# 3DBoard.net
KiCad netlist of a schematic drawn in EAGLE
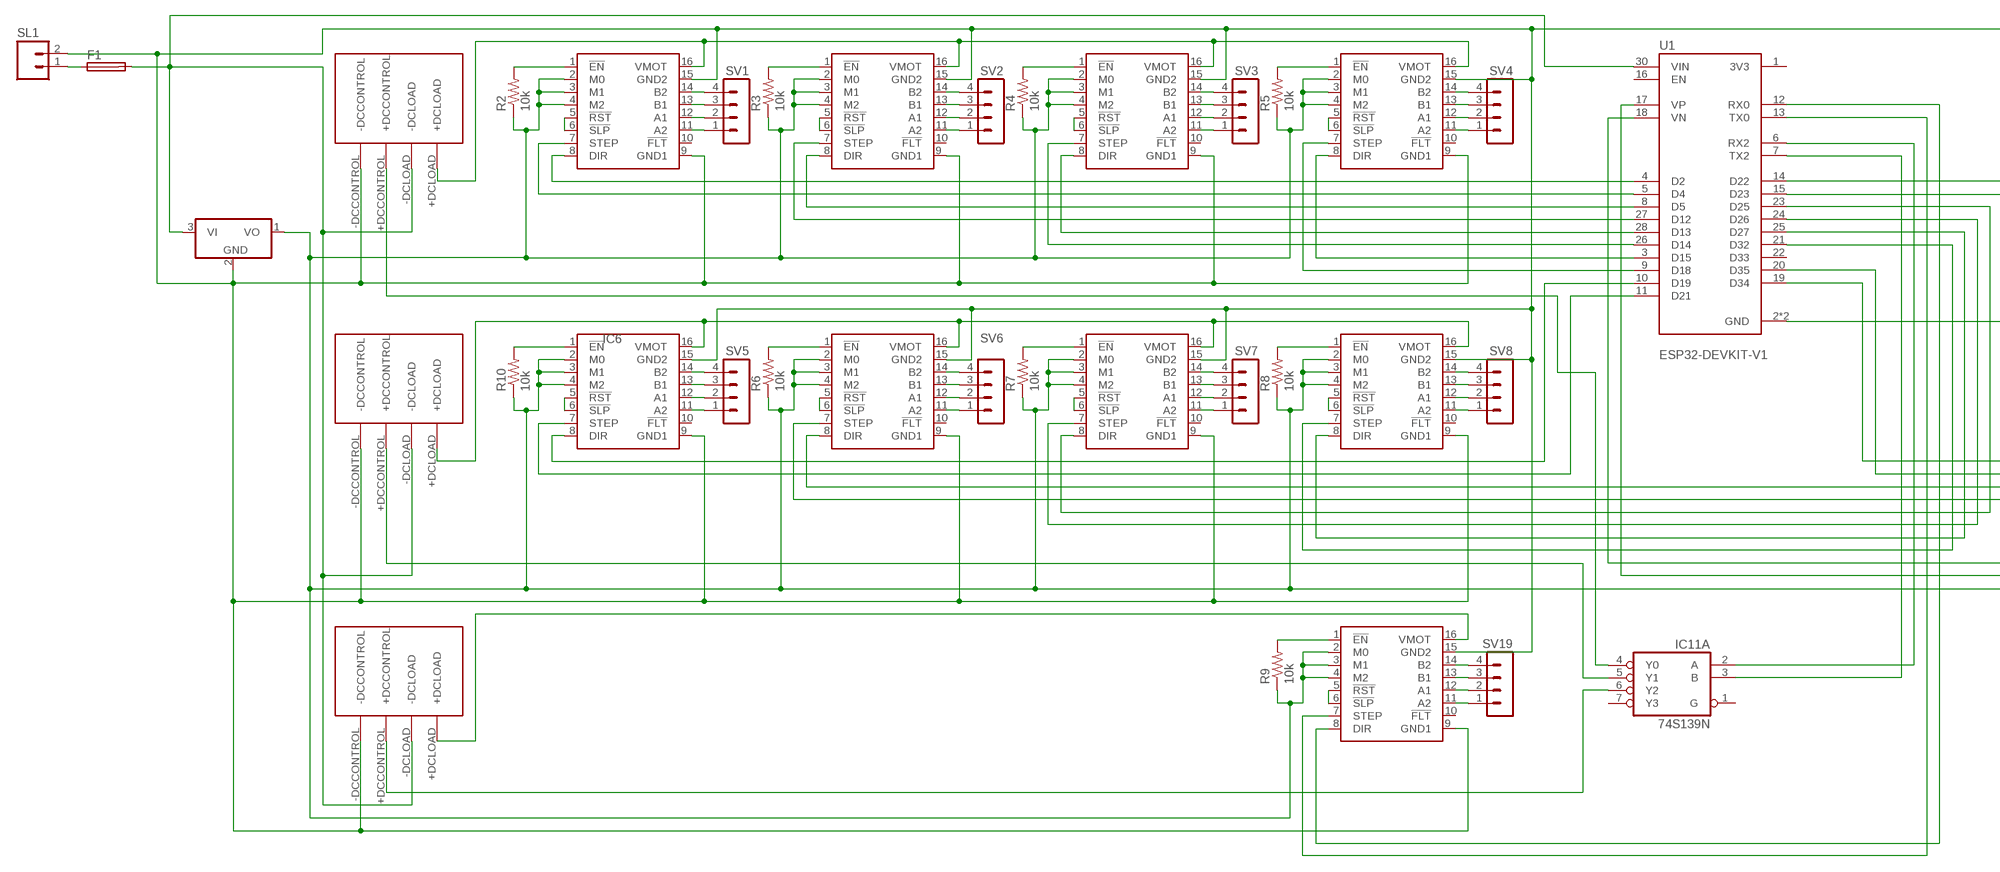
[diagram p0: schematic, sheet 1, part 1 of 2]
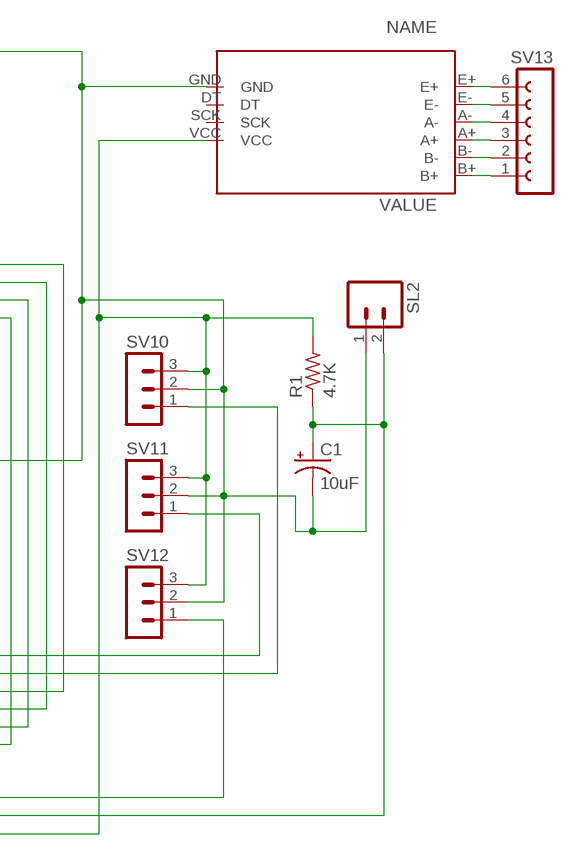
[diagram p1: schematic, sheet 1, part 2 of 2]

(export (version "E")
  (design (tool "Eeschema 10.0.6"))
  (components
    (comp (ref "C1")
      (value "10uF")
      (footprint "eagle-import:B45181B")
      (libsource (lib "eagle-import") (part "CPOL-USB45181B"))
    )
    (comp (ref "F1")
      (value "GSH15")
      (footprint "eagle-import:GSH15")
      (fields (field (name "MPN") "64900001039"))
      (libsource (lib "eagle-import") (part "GSH15"))
    )
    (comp (ref "IC1")
      (value "78L05Z")
      (footprint "eagle-import:TO92")
      (libsource (lib "eagle-import") (part "78ZL05"))
    )
    (comp (ref "IC2")
      (value "2987-DRV8825")
      (footprint "eagle-import:DRV8825")
      (libsource (lib "eagle-import") (part "2987-DRV8825"))
    )
    (comp (ref "IC3")
      (value "2987-DRV8825")
      (footprint "eagle-import:DRV8825")
      (libsource (lib "eagle-import") (part "2987-DRV8825"))
    )
    (comp (ref "IC4")
      (value "2987-DRV8825")
      (footprint "eagle-import:DRV8825")
      (libsource (lib "eagle-import") (part "2987-DRV8825"))
    )
    (comp (ref "IC5")
      (value "2987-DRV8825")
      (footprint "eagle-import:DRV8825")
      (libsource (lib "eagle-import") (part "2987-DRV8825"))
    )
    (comp (ref "IC6")
      (value "2987-DRV8825")
      (footprint "eagle-import:DRV8825")
      (libsource (lib "eagle-import") (part "2987-DRV8825"))
    )
    (comp (ref "IC7")
      (value "2987-DRV8825")
      (footprint "eagle-import:DRV8825")
      (libsource (lib "eagle-import") (part "2987-DRV8825"))
    )
    (comp (ref "IC8")
      (value "2987-DRV8825")
      (footprint "eagle-import:DRV8825")
      (libsource (lib "eagle-import") (part "2987-DRV8825"))
    )
    (comp (ref "IC9")
      (value "2987-DRV8825")
      (footprint "eagle-import:DRV8825")
      (libsource (lib "eagle-import") (part "2987-DRV8825"))
    )
    (comp (ref "IC10")
      (value "2987-DRV8825")
      (footprint "eagle-import:DRV8825")
      (libsource (lib "eagle-import") (part "2987-DRV8825"))
    )
    (comp (ref "IC11")
      (value "74S139N")
      (footprint "eagle-import:DIL16")
      (libsource (lib "eagle-import") (part "74139NS"))
    )
    (comp (ref "R1")
      (value "4.7K")
      (footprint "eagle-import:0204_7")
      (libsource (lib "eagle-import") (part "R-US_0204/7"))
    )
    (comp (ref "R2")
      (value "10k")
      (footprint "eagle-import:0204_7")
      (libsource (lib "eagle-import") (part "R-US_0204/7"))
    )
    (comp (ref "R3")
      (value "10k")
      (footprint "eagle-import:0204_7")
      (libsource (lib "eagle-import") (part "R-US_0204/7"))
    )
    (comp (ref "R4")
      (value "10k")
      (footprint "eagle-import:0204_7")
      (libsource (lib "eagle-import") (part "R-US_0204/7"))
    )
    (comp (ref "R5")
      (value "10k")
      (footprint "eagle-import:0204_7")
      (libsource (lib "eagle-import") (part "R-US_0204/7"))
    )
    (comp (ref "R6")
      (value "10k")
      (footprint "eagle-import:0204_7")
      (libsource (lib "eagle-import") (part "R-US_0204/7"))
    )
    (comp (ref "R7")
      (value "10k")
      (footprint "eagle-import:0204_7")
      (libsource (lib "eagle-import") (part "R-US_0204/7"))
    )
    (comp (ref "R8")
      (value "10k")
      (footprint "eagle-import:0204_7")
      (libsource (lib "eagle-import") (part "R-US_0204/7"))
    )
    (comp (ref "R9")
      (value "10k")
      (footprint "eagle-import:0204_7")
      (libsource (lib "eagle-import") (part "R-US_0204/7"))
    )
    (comp (ref "R10")
      (value "10k")
      (footprint "eagle-import:0204_7")
      (libsource (lib "eagle-import") (part "R-US_0204/7"))
    )
    (comp (ref "SL1")
      (value "M02")
      (footprint "eagle-import:02P")
      (libsource (lib "eagle-import") (part "M02"))
    )
    (comp (ref "SL2")
      (value "M02")
      (footprint "eagle-import:02P")
      (libsource (lib "eagle-import") (part "M02"))
    )
    (comp (ref "SV1")
      (value "MA04-1")
      (footprint "eagle-import:MA04-1")
      (libsource (lib "eagle-import") (part "MA04-1"))
    )
    (comp (ref "SV2")
      (value "MA04-1")
      (footprint "eagle-import:MA04-1")
      (libsource (lib "eagle-import") (part "MA04-1"))
    )
    (comp (ref "SV3")
      (value "MA04-1")
      (footprint "eagle-import:MA04-1")
      (libsource (lib "eagle-import") (part "MA04-1"))
    )
    (comp (ref "SV4")
      (value "MA04-1")
      (footprint "eagle-import:MA04-1")
      (libsource (lib "eagle-import") (part "MA04-1"))
    )
    (comp (ref "SV5")
      (value "MA04-1")
      (footprint "eagle-import:MA04-1")
      (libsource (lib "eagle-import") (part "MA04-1"))
    )
    (comp (ref "SV6")
      (value "MA04-1")
      (footprint "eagle-import:MA04-1")
      (libsource (lib "eagle-import") (part "MA04-1"))
    )
    (comp (ref "SV7")
      (value "MA04-1")
      (footprint "eagle-import:MA04-1")
      (libsource (lib "eagle-import") (part "MA04-1"))
    )
    (comp (ref "SV8")
      (value "MA04-1")
      (footprint "eagle-import:MA04-1")
      (libsource (lib "eagle-import") (part "MA04-1"))
    )
    (comp (ref "SV10")
      (value "MA03-1")
      (footprint "eagle-import:MA03-1")
      (libsource (lib "eagle-import") (part "MA03-1"))
    )
    (comp (ref "SV11")
      (value "MA03-1")
      (footprint "eagle-import:MA03-1")
      (libsource (lib "eagle-import") (part "MA03-1"))
    )
    (comp (ref "SV12")
      (value "MA03-1")
      (footprint "eagle-import:MA03-1")
      (libsource (lib "eagle-import") (part "MA03-1"))
    )
    (comp (ref "SV13")
      (value "FE06-1")
      (footprint "eagle-import:FE06")
      (libsource (lib "eagle-import") (part "FE06-1"))
    )
    (comp (ref "SV19")
      (value "MA04-1")
      (footprint "eagle-import:MA04-1")
      (libsource (lib "eagle-import") (part "MA04-1"))
    )
    (comp (ref "U$2")
      (value "HX711A")
      (footprint "eagle-import:HX711")
      (libsource (lib "eagle-import") (part "HX711A"))
    )
    (comp (ref "U$3")
      (value "CMX60D10")
      (footprint "eagle-import:SIP-4")
      (fields (field (name "MF") "Sensata-Crydom"))
      (libsource (lib "eagle-import") (part "CMX60D10"))
    )
    (comp (ref "U$4")
      (value "CMX60D10")
      (footprint "eagle-import:SIP-4")
      (fields (field (name "MF") "Sensata-Crydom"))
      (libsource (lib "eagle-import") (part "CMX60D10"))
    )
    (comp (ref "U$5")
      (value "CMX60D10")
      (footprint "eagle-import:SIP-4")
      (fields (field (name "MF") "Sensata-Crydom"))
      (libsource (lib "eagle-import") (part "CMX60D10"))
    )
    (comp (ref "U1")
      (value "ESP32-DEVKIT-V1")
      (footprint "eagle-import:MODULE_ESP32_DEVKIT_V1")
      (fields (field (name "MF") "Do it"))
      (libsource (lib "eagle-import") (part "ESP32-DEVKIT-V1"))
    )
  )
  (nets
    (net (code "1") (name "Net-(F1-Pad1)") (class "Default")
      (node (ref "F1") (pin "1") (pinfunction "1_1") (pintype "passive"))
      (node (ref "SL1") (pin "1") (pinfunction "1_1") (pintype "passive"))
    )
    (net (code "2") (name "Net-(IC1-GND)") (class "Default")
      (node (ref "C1") (pin "-") (pinfunction "-_-") (pintype "passive"))
      (node (ref "IC1") (pin "2") (pinfunction "GND_2") (pintype "passive"))
      (node (ref "IC10") (pin "15") (pinfunction "GND2_15") (pintype "power_in"))
      (node (ref "IC10") (pin "9") (pinfunction "GND1_9") (pintype "power_in"))
      (node (ref "IC2") (pin "15") (pinfunction "GND2_15") (pintype "power_in"))
      (node (ref "IC2") (pin "9") (pinfunction "GND1_9") (pintype "power_in"))
      (node (ref "IC3") (pin "15") (pinfunction "GND2_15") (pintype "power_in"))
      (node (ref "IC3") (pin "9") (pinfunction "GND1_9") (pintype "power_in"))
      (node (ref "IC4") (pin "15") (pinfunction "GND2_15") (pintype "power_in"))
      (node (ref "IC4") (pin "9") (pinfunction "GND1_9") (pintype "power_in"))
      (node (ref "IC5") (pin "15") (pinfunction "GND2_15") (pintype "power_in"))
      (node (ref "IC5") (pin "9") (pinfunction "GND1_9") (pintype "power_in"))
      (node (ref "IC6") (pin "15") (pinfunction "GND2_15") (pintype "power_in"))
      (node (ref "IC6") (pin "9") (pinfunction "GND1_9") (pintype "power_in"))
      (node (ref "IC7") (pin "15") (pinfunction "GND2_15") (pintype "power_in"))
      (node (ref "IC7") (pin "9") (pinfunction "GND1_9") (pintype "power_in"))
      (node (ref "IC8") (pin "15") (pinfunction "GND2_15") (pintype "power_in"))
      (node (ref "IC8") (pin "9") (pinfunction "GND1_9") (pintype "power_in"))
      (node (ref "IC9") (pin "15") (pinfunction "GND2_15") (pintype "power_in"))
      (node (ref "IC9") (pin "9") (pinfunction "GND1_9") (pintype "power_in"))
      (node (ref "SL1") (pin "2") (pinfunction "2_2") (pintype "passive"))
      (node (ref "SL2") (pin "1") (pinfunction "1_1") (pintype "passive"))
      (node (ref "SV10") (pin "2") (pinfunction "2_2") (pintype "passive"))
      (node (ref "SV11") (pin "2") (pinfunction "2_2") (pintype "passive"))
      (node (ref "SV12") (pin "2") (pinfunction "2_2") (pintype "passive"))
      (node (ref "U$2") (pin "GND") (pinfunction "GND_GND") (pintype "bidirectional"))
      (node (ref "U$3") (pin "-DCCONTROL") (pinfunction "-DCCONTROL_-DCCONTROL") (pintype "bidirectional"))
      (node (ref "U$4") (pin "-DCCONTROL") (pinfunction "-DCCONTROL_-DCCONTROL") (pintype "bidirectional"))
      (node (ref "U$5") (pin "-DCCONTROL") (pinfunction "-DCCONTROL_-DCCONTROL") (pintype "bidirectional"))
      (node (ref "U1") (pin "2") (pinfunction "GND_2") (pintype "power_in"))
      (node (ref "U1") (pin "29") (pinfunction "GND_29") (pintype "power_in"))
    )
    (net (code "3") (name "Net-(IC1-VI)") (class "Default")
      (node (ref "F1") (pin "2") (pinfunction "2_2") (pintype "passive"))
      (node (ref "IC1") (pin "3") (pinfunction "VI_3") (pintype "input"))
      (node (ref "U$3") (pin "-DCLOAD") (pinfunction "-DCLOAD_-DCLOAD") (pintype "bidirectional"))
      (node (ref "U$4") (pin "-DCLOAD") (pinfunction "-DCLOAD_-DCLOAD") (pintype "bidirectional"))
      (node (ref "U$5") (pin "-DCLOAD") (pinfunction "-DCLOAD_-DCLOAD") (pintype "bidirectional"))
      (node (ref "U1") (pin "30") (pinfunction "VIN_30") (pintype "input"))
    )
    (net (code "4") (name "Net-(IC1-VO)") (class "Default")
      (node (ref "IC1") (pin "1") (pinfunction "VO_1") (pintype "passive"))
      (node (ref "IC10") (pin "2") (pinfunction "M0_2") (pintype "passive"))
      (node (ref "IC10") (pin "3") (pinfunction "M1_3") (pintype "passive"))
      (node (ref "IC10") (pin "4") (pinfunction "M2_4") (pintype "passive"))
      (node (ref "IC2") (pin "2") (pinfunction "M0_2") (pintype "passive"))
      (node (ref "IC2") (pin "3") (pinfunction "M1_3") (pintype "passive"))
      (node (ref "IC2") (pin "4") (pinfunction "M2_4") (pintype "passive"))
      (node (ref "IC3") (pin "2") (pinfunction "M0_2") (pintype "passive"))
      (node (ref "IC3") (pin "3") (pinfunction "M1_3") (pintype "passive"))
      (node (ref "IC3") (pin "4") (pinfunction "M2_4") (pintype "passive"))
      (node (ref "IC4") (pin "2") (pinfunction "M0_2") (pintype "passive"))
      (node (ref "IC4") (pin "3") (pinfunction "M1_3") (pintype "passive"))
      (node (ref "IC4") (pin "4") (pinfunction "M2_4") (pintype "passive"))
      (node (ref "IC5") (pin "2") (pinfunction "M0_2") (pintype "passive"))
      (node (ref "IC5") (pin "3") (pinfunction "M1_3") (pintype "passive"))
      (node (ref "IC5") (pin "4") (pinfunction "M2_4") (pintype "passive"))
      (node (ref "IC6") (pin "2") (pinfunction "M0_2") (pintype "passive"))
      (node (ref "IC6") (pin "3") (pinfunction "M1_3") (pintype "passive"))
      (node (ref "IC6") (pin "4") (pinfunction "M2_4") (pintype "passive"))
      (node (ref "IC7") (pin "2") (pinfunction "M0_2") (pintype "passive"))
      (node (ref "IC7") (pin "3") (pinfunction "M1_3") (pintype "passive"))
      (node (ref "IC7") (pin "4") (pinfunction "M2_4") (pintype "passive"))
      (node (ref "IC8") (pin "2") (pinfunction "M0_2") (pintype "passive"))
      (node (ref "IC8") (pin "3") (pinfunction "M1_3") (pintype "passive"))
      (node (ref "IC8") (pin "4") (pinfunction "M2_4") (pintype "passive"))
      (node (ref "IC9") (pin "2") (pinfunction "M0_2") (pintype "passive"))
      (node (ref "IC9") (pin "3") (pinfunction "M1_3") (pintype "passive"))
      (node (ref "IC9") (pin "4") (pinfunction "M2_4") (pintype "passive"))
      (node (ref "R1") (pin "2") (pinfunction "2_2") (pintype "passive"))
      (node (ref "R10") (pin "1") (pinfunction "1_1") (pintype "passive"))
      (node (ref "R2") (pin "1") (pinfunction "1_1") (pintype "passive"))
      (node (ref "R3") (pin "1") (pinfunction "1_1") (pintype "passive"))
      (node (ref "R4") (pin "1") (pinfunction "1_1") (pintype "passive"))
      (node (ref "R5") (pin "1") (pinfunction "1_1") (pintype "passive"))
      (node (ref "R6") (pin "1") (pinfunction "1_1") (pintype "passive"))
      (node (ref "R7") (pin "1") (pinfunction "1_1") (pintype "passive"))
      (node (ref "R8") (pin "1") (pinfunction "1_1") (pintype "passive"))
      (node (ref "R9") (pin "1") (pinfunction "1_1") (pintype "passive"))
      (node (ref "SV10") (pin "3") (pinfunction "3_3") (pintype "passive"))
      (node (ref "SV11") (pin "3") (pinfunction "3_3") (pintype "passive"))
      (node (ref "SV12") (pin "3") (pinfunction "3_3") (pintype "passive"))
      (node (ref "U$2") (pin "VCC") (pinfunction "VCC_VCC") (pintype "bidirectional"))
    )
    (net (code "5") (name "Net-(IC2-A1)") (class "Default")
      (node (ref "IC2") (pin "12") (pinfunction "A1_12") (pintype "output"))
      (node (ref "SV1") (pin "2") (pinfunction "2_2") (pintype "passive"))
    )
    (net (code "6") (name "Net-(IC2-A2)") (class "Default")
      (node (ref "IC2") (pin "11") (pinfunction "A2_11") (pintype "output"))
      (node (ref "SV1") (pin "1") (pinfunction "1_1") (pintype "passive"))
    )
    (net (code "7") (name "Net-(IC2-B1)") (class "Default")
      (node (ref "IC2") (pin "13") (pinfunction "B1_13") (pintype "output"))
      (node (ref "SV1") (pin "3") (pinfunction "3_3") (pintype "passive"))
    )
    (net (code "8") (name "Net-(IC2-B2)") (class "Default")
      (node (ref "IC2") (pin "14") (pinfunction "B2_14") (pintype "output"))
      (node (ref "SV1") (pin "4") (pinfunction "4_4") (pintype "passive"))
    )
    (net (code "9") (name "Net-(IC2-DIR)") (class "Default")
      (node (ref "IC2") (pin "8") (pinfunction "DIR_8") (pintype "input"))
      (node (ref "U1") (pin "4") (pinfunction "D2_4") (pintype "bidirectional"))
    )
    (net (code "10") (name "Net-(IC2-STEP)") (class "Default")
      (node (ref "IC2") (pin "7") (pinfunction "STEP_7") (pintype "input"))
      (node (ref "U1") (pin "5") (pinfunction "D4_5") (pintype "bidirectional"))
    )
    (net (code "11") (name "Net-(IC2-VMOT)") (class "Default")
      (node (ref "IC2") (pin "16") (pinfunction "VMOT_16") (pintype "power_in"))
      (node (ref "IC3") (pin "16") (pinfunction "VMOT_16") (pintype "power_in"))
      (node (ref "IC4") (pin "16") (pinfunction "VMOT_16") (pintype "power_in"))
      (node (ref "IC5") (pin "16") (pinfunction "VMOT_16") (pintype "power_in"))
      (node (ref "U$3") (pin "+DCLOAD") (pinfunction "+DCLOAD_+DCLOAD") (pintype "bidirectional"))
    )
    (net (code "12") (name "Net-(IC2-~{EN})") (class "Default")
      (node (ref "IC2") (pin "1") (pinfunction "~{EN}_1") (pintype "passive"))
      (node (ref "R2") (pin "2") (pinfunction "2_2") (pintype "passive"))
    )
    (net (code "13") (name "Net-(IC2-~{RST})") (class "Default")
      (node (ref "IC2") (pin "5") (pinfunction "~{RST}_5") (pintype "input"))
      (node (ref "IC2") (pin "6") (pinfunction "~{SLP}_6") (pintype "input"))
    )
    (net (code "14") (name "Net-(IC3-A1)") (class "Default")
      (node (ref "IC3") (pin "12") (pinfunction "A1_12") (pintype "output"))
      (node (ref "SV2") (pin "2") (pinfunction "2_2") (pintype "passive"))
    )
    (net (code "15") (name "Net-(IC3-A2)") (class "Default")
      (node (ref "IC3") (pin "11") (pinfunction "A2_11") (pintype "output"))
      (node (ref "SV2") (pin "1") (pinfunction "1_1") (pintype "passive"))
    )
    (net (code "16") (name "Net-(IC3-B1)") (class "Default")
      (node (ref "IC3") (pin "13") (pinfunction "B1_13") (pintype "output"))
      (node (ref "SV2") (pin "3") (pinfunction "3_3") (pintype "passive"))
    )
    (net (code "17") (name "Net-(IC3-B2)") (class "Default")
      (node (ref "IC3") (pin "14") (pinfunction "B2_14") (pintype "output"))
      (node (ref "SV2") (pin "4") (pinfunction "4_4") (pintype "passive"))
    )
    (net (code "18") (name "Net-(IC3-DIR)") (class "Default")
      (node (ref "IC3") (pin "8") (pinfunction "DIR_8") (pintype "input"))
      (node (ref "U1") (pin "8") (pinfunction "D5_8") (pintype "bidirectional"))
    )
    (net (code "19") (name "Net-(IC3-STEP)") (class "Default")
      (node (ref "IC3") (pin "7") (pinfunction "STEP_7") (pintype "input"))
      (node (ref "U1") (pin "27") (pinfunction "D12_27") (pintype "bidirectional"))
    )
    (net (code "20") (name "Net-(IC3-~{EN})") (class "Default")
      (node (ref "IC3") (pin "1") (pinfunction "~{EN}_1") (pintype "passive"))
      (node (ref "R3") (pin "2") (pinfunction "2_2") (pintype "passive"))
    )
    (net (code "21") (name "Net-(IC3-~{RST})") (class "Default")
      (node (ref "IC3") (pin "5") (pinfunction "~{RST}_5") (pintype "input"))
      (node (ref "IC3") (pin "6") (pinfunction "~{SLP}_6") (pintype "input"))
    )
    (net (code "22") (name "Net-(IC4-A1)") (class "Default")
      (node (ref "IC4") (pin "12") (pinfunction "A1_12") (pintype "output"))
      (node (ref "SV3") (pin "2") (pinfunction "2_2") (pintype "passive"))
    )
    (net (code "23") (name "Net-(IC4-A2)") (class "Default")
      (node (ref "IC4") (pin "11") (pinfunction "A2_11") (pintype "output"))
      (node (ref "SV3") (pin "1") (pinfunction "1_1") (pintype "passive"))
    )
    (net (code "24") (name "Net-(IC4-B1)") (class "Default")
      (node (ref "IC4") (pin "13") (pinfunction "B1_13") (pintype "output"))
      (node (ref "SV3") (pin "3") (pinfunction "3_3") (pintype "passive"))
    )
    (net (code "25") (name "Net-(IC4-B2)") (class "Default")
      (node (ref "IC4") (pin "14") (pinfunction "B2_14") (pintype "output"))
      (node (ref "SV3") (pin "4") (pinfunction "4_4") (pintype "passive"))
    )
    (net (code "26") (name "Net-(IC4-DIR)") (class "Default")
      (node (ref "IC4") (pin "8") (pinfunction "DIR_8") (pintype "input"))
      (node (ref "U1") (pin "28") (pinfunction "D13_28") (pintype "bidirectional"))
    )
    (net (code "27") (name "Net-(IC4-STEP)") (class "Default")
      (node (ref "IC4") (pin "7") (pinfunction "STEP_7") (pintype "input"))
      (node (ref "U1") (pin "26") (pinfunction "D14_26") (pintype "bidirectional"))
    )
    (net (code "28") (name "Net-(IC4-~{EN})") (class "Default")
      (node (ref "IC4") (pin "1") (pinfunction "~{EN}_1") (pintype "passive"))
      (node (ref "R4") (pin "2") (pinfunction "2_2") (pintype "passive"))
    )
    (net (code "29") (name "Net-(IC4-~{RST})") (class "Default")
      (node (ref "IC4") (pin "5") (pinfunction "~{RST}_5") (pintype "input"))
      (node (ref "IC4") (pin "6") (pinfunction "~{SLP}_6") (pintype "input"))
    )
    (net (code "30") (name "Net-(IC5-A1)") (class "Default")
      (node (ref "IC5") (pin "12") (pinfunction "A1_12") (pintype "output"))
      (node (ref "SV4") (pin "2") (pinfunction "2_2") (pintype "passive"))
    )
    (net (code "31") (name "Net-(IC5-A2)") (class "Default")
      (node (ref "IC5") (pin "11") (pinfunction "A2_11") (pintype "output"))
      (node (ref "SV4") (pin "1") (pinfunction "1_1") (pintype "passive"))
    )
    (net (code "32") (name "Net-(IC5-B1)") (class "Default")
      (node (ref "IC5") (pin "13") (pinfunction "B1_13") (pintype "output"))
      (node (ref "SV4") (pin "3") (pinfunction "3_3") (pintype "passive"))
    )
    (net (code "33") (name "Net-(IC5-B2)") (class "Default")
      (node (ref "IC5") (pin "14") (pinfunction "B2_14") (pintype "output"))
      (node (ref "SV4") (pin "4") (pinfunction "4_4") (pintype "passive"))
    )
    (net (code "34") (name "Net-(IC5-DIR)") (class "Default")
      (node (ref "IC5") (pin "8") (pinfunction "DIR_8") (pintype "input"))
      (node (ref "U1") (pin "3") (pinfunction "D15_3") (pintype "bidirectional"))
    )
    (net (code "35") (name "Net-(IC5-STEP)") (class "Default")
      (node (ref "IC5") (pin "7") (pinfunction "STEP_7") (pintype "input"))
      (node (ref "U1") (pin "9") (pinfunction "D18_9") (pintype "bidirectional"))
    )
    (net (code "36") (name "Net-(IC5-~{EN})") (class "Default")
      (node (ref "IC5") (pin "1") (pinfunction "~{EN}_1") (pintype "passive"))
      (node (ref "R5") (pin "2") (pinfunction "2_2") (pintype "passive"))
    )
    (net (code "37") (name "Net-(IC5-~{RST})") (class "Default")
      (node (ref "IC5") (pin "5") (pinfunction "~{RST}_5") (pintype "input"))
      (node (ref "IC5") (pin "6") (pinfunction "~{SLP}_6") (pintype "input"))
    )
    (net (code "38") (name "Net-(IC6-A1)") (class "Default")
      (node (ref "IC6") (pin "12") (pinfunction "A1_12") (pintype "output"))
      (node (ref "SV5") (pin "2") (pinfunction "2_2") (pintype "passive"))
    )
    (net (code "39") (name "Net-(IC6-A2)") (class "Default")
      (node (ref "IC6") (pin "11") (pinfunction "A2_11") (pintype "output"))
      (node (ref "SV5") (pin "1") (pinfunction "1_1") (pintype "passive"))
    )
    (net (code "40") (name "Net-(IC6-B1)") (class "Default")
      (node (ref "IC6") (pin "13") (pinfunction "B1_13") (pintype "output"))
      (node (ref "SV5") (pin "3") (pinfunction "3_3") (pintype "passive"))
    )
    (net (code "41") (name "Net-(IC6-B2)") (class "Default")
      (node (ref "IC6") (pin "14") (pinfunction "B2_14") (pintype "output"))
      (node (ref "SV5") (pin "4") (pinfunction "4_4") (pintype "passive"))
    )
    (net (code "42") (name "Net-(IC6-DIR)") (class "Default")
      (node (ref "IC6") (pin "8") (pinfunction "DIR_8") (pintype "input"))
      (node (ref "U1") (pin "10") (pinfunction "D19_10") (pintype "bidirectional"))
    )
    (net (code "43") (name "Net-(IC6-STEP)") (class "Default")
      (node (ref "IC6") (pin "7") (pinfunction "STEP_7") (pintype "input"))
      (node (ref "U1") (pin "11") (pinfunction "D21_11") (pintype "bidirectional"))
    )
    (net (code "44") (name "Net-(IC6-VMOT)") (class "Default")
      (node (ref "IC6") (pin "16") (pinfunction "VMOT_16") (pintype "power_in"))
      (node (ref "IC7") (pin "16") (pinfunction "VMOT_16") (pintype "power_in"))
      (node (ref "IC8") (pin "16") (pinfunction "VMOT_16") (pintype "power_in"))
      (node (ref "IC9") (pin "16") (pinfunction "VMOT_16") (pintype "power_in"))
      (node (ref "U$4") (pin "+DCLOAD") (pinfunction "+DCLOAD_+DCLOAD") (pintype "bidirectional"))
    )
    (net (code "45") (name "Net-(IC6-~{EN})") (class "Default")
      (node (ref "IC6") (pin "1") (pinfunction "~{EN}_1") (pintype "passive"))
      (node (ref "R10") (pin "2") (pinfunction "2_2") (pintype "passive"))
    )
    (net (code "46") (name "Net-(IC6-~{RST})") (class "Default")
      (node (ref "IC6") (pin "5") (pinfunction "~{RST}_5") (pintype "input"))
      (node (ref "IC6") (pin "6") (pinfunction "~{SLP}_6") (pintype "input"))
    )
    (net (code "47") (name "Net-(IC7-A1)") (class "Default")
      (node (ref "IC7") (pin "12") (pinfunction "A1_12") (pintype "output"))
      (node (ref "SV6") (pin "2") (pinfunction "2_2") (pintype "passive"))
    )
    (net (code "48") (name "Net-(IC7-A2)") (class "Default")
      (node (ref "IC7") (pin "11") (pinfunction "A2_11") (pintype "output"))
      (node (ref "SV6") (pin "1") (pinfunction "1_1") (pintype "passive"))
    )
    (net (code "49") (name "Net-(IC7-B1)") (class "Default")
      (node (ref "IC7") (pin "13") (pinfunction "B1_13") (pintype "output"))
      (node (ref "SV6") (pin "3") (pinfunction "3_3") (pintype "passive"))
    )
    (net (code "50") (name "Net-(IC7-B2)") (class "Default")
      (node (ref "IC7") (pin "14") (pinfunction "B2_14") (pintype "output"))
      (node (ref "SV6") (pin "4") (pinfunction "4_4") (pintype "passive"))
    )
    (net (code "51") (name "Net-(IC7-DIR)") (class "Default")
      (node (ref "IC7") (pin "8") (pinfunction "DIR_8") (pintype "input"))
      (node (ref "U1") (pin "14") (pinfunction "D22_14") (pintype "bidirectional"))
    )
    (net (code "52") (name "Net-(IC7-STEP)") (class "Default")
      (node (ref "IC7") (pin "7") (pinfunction "STEP_7") (pintype "input"))
      (node (ref "U1") (pin "15") (pinfunction "D23_15") (pintype "bidirectional"))
    )
    (net (code "53") (name "Net-(IC7-~{EN})") (class "Default")
      (node (ref "IC7") (pin "1") (pinfunction "~{EN}_1") (pintype "passive"))
      (node (ref "R6") (pin "2") (pinfunction "2_2") (pintype "passive"))
    )
    (net (code "54") (name "Net-(IC7-~{RST})") (class "Default")
      (node (ref "IC7") (pin "5") (pinfunction "~{RST}_5") (pintype "input"))
      (node (ref "IC7") (pin "6") (pinfunction "~{SLP}_6") (pintype "input"))
    )
    (net (code "55") (name "Net-(IC8-A1)") (class "Default")
      (node (ref "IC8") (pin "12") (pinfunction "A1_12") (pintype "output"))
      (node (ref "SV7") (pin "2") (pinfunction "2_2") (pintype "passive"))
    )
    (net (code "56") (name "Net-(IC8-A2)") (class "Default")
      (node (ref "IC8") (pin "11") (pinfunction "A2_11") (pintype "output"))
      (node (ref "SV7") (pin "1") (pinfunction "1_1") (pintype "passive"))
    )
    (net (code "57") (name "Net-(IC8-B1)") (class "Default")
      (node (ref "IC8") (pin "13") (pinfunction "B1_13") (pintype "output"))
      (node (ref "SV7") (pin "3") (pinfunction "3_3") (pintype "passive"))
    )
    (net (code "58") (name "Net-(IC8-B2)") (class "Default")
      (node (ref "IC8") (pin "14") (pinfunction "B2_14") (pintype "output"))
      (node (ref "SV7") (pin "4") (pinfunction "4_4") (pintype "passive"))
    )
    (net (code "59") (name "Net-(IC8-DIR)") (class "Default")
      (node (ref "IC8") (pin "8") (pinfunction "DIR_8") (pintype "input"))
      (node (ref "U1") (pin "23") (pinfunction "D25_23") (pintype "bidirectional"))
    )
    (net (code "60") (name "Net-(IC8-STEP)") (class "Default")
      (node (ref "IC8") (pin "7") (pinfunction "STEP_7") (pintype "input"))
      (node (ref "U1") (pin "24") (pinfunction "D26_24") (pintype "bidirectional"))
    )
    (net (code "61") (name "Net-(IC8-~{EN})") (class "Default")
      (node (ref "IC8") (pin "1") (pinfunction "~{EN}_1") (pintype "passive"))
      (node (ref "R7") (pin "2") (pinfunction "2_2") (pintype "passive"))
    )
    (net (code "62") (name "Net-(IC8-~{RST})") (class "Default")
      (node (ref "IC8") (pin "5") (pinfunction "~{RST}_5") (pintype "input"))
      (node (ref "IC8") (pin "6") (pinfunction "~{SLP}_6") (pintype "input"))
    )
    (net (code "63") (name "Net-(IC9-A1)") (class "Default")
      (node (ref "IC9") (pin "12") (pinfunction "A1_12") (pintype "output"))
      (node (ref "SV8") (pin "2") (pinfunction "2_2") (pintype "passive"))
    )
    (net (code "64") (name "Net-(IC9-A2)") (class "Default")
      (node (ref "IC9") (pin "11") (pinfunction "A2_11") (pintype "output"))
      (node (ref "SV8") (pin "1") (pinfunction "1_1") (pintype "passive"))
    )
    (net (code "65") (name "Net-(IC9-B1)") (class "Default")
      (node (ref "IC9") (pin "13") (pinfunction "B1_13") (pintype "output"))
      (node (ref "SV8") (pin "3") (pinfunction "3_3") (pintype "passive"))
    )
    (net (code "66") (name "Net-(IC9-B2)") (class "Default")
      (node (ref "IC9") (pin "14") (pinfunction "B2_14") (pintype "output"))
      (node (ref "SV8") (pin "4") (pinfunction "4_4") (pintype "passive"))
    )
    (net (code "67") (name "Net-(IC9-DIR)") (class "Default")
      (node (ref "IC9") (pin "8") (pinfunction "DIR_8") (pintype "input"))
      (node (ref "U1") (pin "25") (pinfunction "D27_25") (pintype "bidirectional"))
    )
    (net (code "68") (name "Net-(IC9-STEP)") (class "Default")
      (node (ref "IC9") (pin "7") (pinfunction "STEP_7") (pintype "input"))
      (node (ref "U1") (pin "21") (pinfunction "D32_21") (pintype "bidirectional"))
    )
    (net (code "69") (name "Net-(IC9-~{EN})") (class "Default")
      (node (ref "IC9") (pin "1") (pinfunction "~{EN}_1") (pintype "passive"))
      (node (ref "R8") (pin "2") (pinfunction "2_2") (pintype "passive"))
    )
    (net (code "70") (name "Net-(IC9-~{RST})") (class "Default")
      (node (ref "IC9") (pin "5") (pinfunction "~{RST}_5") (pintype "input"))
      (node (ref "IC9") (pin "6") (pinfunction "~{SLP}_6") (pintype "input"))
    )
    (net (code "71") (name "Net-(IC10-A1)") (class "Default")
      (node (ref "IC10") (pin "12") (pinfunction "A1_12") (pintype "output"))
      (node (ref "SV19") (pin "2") (pinfunction "2_2") (pintype "passive"))
    )
    (net (code "72") (name "Net-(IC10-A2)") (class "Default")
      (node (ref "IC10") (pin "11") (pinfunction "A2_11") (pintype "output"))
      (node (ref "SV19") (pin "1") (pinfunction "1_1") (pintype "passive"))
    )
    (net (code "73") (name "Net-(IC10-B1)") (class "Default")
      (node (ref "IC10") (pin "13") (pinfunction "B1_13") (pintype "output"))
      (node (ref "SV19") (pin "3") (pinfunction "3_3") (pintype "passive"))
    )
    (net (code "74") (name "Net-(IC10-B2)") (class "Default")
      (node (ref "IC10") (pin "14") (pinfunction "B2_14") (pintype "output"))
      (node (ref "SV19") (pin "4") (pinfunction "4_4") (pintype "passive"))
    )
    (net (code "75") (name "Net-(IC10-DIR)") (class "Default")
      (node (ref "IC10") (pin "8") (pinfunction "DIR_8") (pintype "input"))
      (node (ref "U1") (pin "12") (pinfunction "RX0_12") (pintype "input"))
    )
    (net (code "76") (name "Net-(IC10-STEP)") (class "Default")
      (node (ref "IC10") (pin "7") (pinfunction "STEP_7") (pintype "input"))
      (node (ref "U1") (pin "13") (pinfunction "TX0_13") (pintype "output"))
    )
    (net (code "77") (name "Net-(IC10-VMOT)") (class "Default")
      (node (ref "IC10") (pin "16") (pinfunction "VMOT_16") (pintype "power_in"))
      (node (ref "U$5") (pin "+DCLOAD") (pinfunction "+DCLOAD_+DCLOAD") (pintype "bidirectional"))
    )
    (net (code "78") (name "Net-(IC10-~{EN})") (class "Default")
      (node (ref "IC10") (pin "1") (pinfunction "~{EN}_1") (pintype "passive"))
      (node (ref "R9") (pin "2") (pinfunction "2_2") (pintype "passive"))
    )
    (net (code "79") (name "Net-(IC10-~{RST})") (class "Default")
      (node (ref "IC10") (pin "5") (pinfunction "~{RST}_5") (pintype "input"))
      (node (ref "IC10") (pin "6") (pinfunction "~{SLP}_6") (pintype "input"))
    )
    (net (code "80") (name "Net-(IC11A-A)") (class "Default")
      (node (ref "IC11") (pin "2") (pinfunction "A_2") (pintype "input"))
      (node (ref "U1") (pin "6") (pinfunction "RX2_6") (pintype "input"))
    )
    (net (code "81") (name "Net-(IC11A-B)") (class "Default")
      (node (ref "IC11") (pin "3") (pinfunction "B_3") (pintype "input"))
      (node (ref "U1") (pin "7") (pinfunction "TX2_7") (pintype "output"))
    )
    (net (code "82") (name "Net-(IC11A-Y0)") (class "Default")
      (node (ref "IC11") (pin "4") (pinfunction "Y0_4") (pintype "output"))
      (node (ref "U$3") (pin "+DCCONTROL") (pinfunction "+DCCONTROL_+DCCONTROL") (pintype "bidirectional"))
    )
    (net (code "83") (name "Net-(IC11A-Y1)") (class "Default")
      (node (ref "IC11") (pin "5") (pinfunction "Y1_5") (pintype "output"))
      (node (ref "U$4") (pin "+DCCONTROL") (pinfunction "+DCCONTROL_+DCCONTROL") (pintype "bidirectional"))
    )
    (net (code "84") (name "Net-(IC11A-Y2)") (class "Default")
      (node (ref "IC11") (pin "6") (pinfunction "Y2_6") (pintype "output"))
      (node (ref "U$5") (pin "+DCCONTROL") (pinfunction "+DCCONTROL_+DCCONTROL") (pintype "bidirectional"))
    )
    (net (code "85") (name "Net-(SV13-Pad1)") (class "Default")
      (node (ref "SV13") (pin "1") (pinfunction "1_1") (pintype "passive"))
      (node (ref "U$2") (pin "B+") (pinfunction "B+_B+") (pintype "bidirectional"))
    )
    (net (code "86") (name "Net-(SV13-Pad2)") (class "Default")
      (node (ref "SV13") (pin "2") (pinfunction "2_2") (pintype "passive"))
      (node (ref "U$2") (pin "B-") (pinfunction "B-_B-") (pintype "bidirectional"))
    )
    (net (code "87") (name "Net-(SV13-Pad3)") (class "Default")
      (node (ref "SV13") (pin "3") (pinfunction "3_3") (pintype "passive"))
      (node (ref "U$2") (pin "A+") (pinfunction "A+_A+") (pintype "bidirectional"))
    )
    (net (code "88") (name "Net-(SV13-Pad4)") (class "Default")
      (node (ref "SV13") (pin "4") (pinfunction "4_4") (pintype "passive"))
      (node (ref "U$2") (pin "A-") (pinfunction "A-_A-") (pintype "bidirectional"))
    )
    (net (code "89") (name "Net-(SV13-Pad5)") (class "Default")
      (node (ref "SV13") (pin "5") (pinfunction "5_5") (pintype "passive"))
      (node (ref "U$2") (pin "E-") (pinfunction "E-_E-") (pintype "bidirectional"))
    )
    (net (code "90") (name "Net-(SV13-Pad6)") (class "Default")
      (node (ref "SV13") (pin "6") (pinfunction "6_6") (pintype "passive"))
      (node (ref "U$2") (pin "E+") (pinfunction "E+_E+") (pintype "bidirectional"))
    )
    (net (code "91") (name "Net-(U1-D34)") (class "Default")
      (node (ref "SV11") (pin "1") (pinfunction "1_1") (pintype "passive"))
      (node (ref "U1") (pin "19") (pinfunction "D34_19") (pintype "bidirectional"))
    )
    (net (code "92") (name "Net-(U1-D35)") (class "Default")
      (node (ref "SV10") (pin "1") (pinfunction "1_1") (pintype "passive"))
      (node (ref "U1") (pin "20") (pinfunction "D35_20") (pintype "bidirectional"))
    )
    (net (code "93") (name "Net-(U1-VN)") (class "Default")
      (node (ref "SV12") (pin "1") (pinfunction "1_1") (pintype "passive"))
      (node (ref "U1") (pin "18") (pinfunction "VN_18") (pintype "bidirectional"))
    )
    (net (code "94") (name "Net-(U1-VP)") (class "Default")
      (node (ref "C1") (pin "+") (pinfunction "+_+") (pintype "passive"))
      (node (ref "R1") (pin "1") (pinfunction "1_1") (pintype "passive"))
      (node (ref "SL2") (pin "2") (pinfunction "2_2") (pintype "passive"))
      (node (ref "U1") (pin "17") (pinfunction "VP_17") (pintype "bidirectional"))
    )
    (net (code "95") (name "unconnected-(IC2-~{FLT}-Pad10)") (class "Default")
      (node (ref "IC2") (pin "10") (pinfunction "~{FLT}_10") (pintype "open_collector"))
    )
    (net (code "96") (name "unconnected-(IC3-~{FLT}-Pad10)") (class "Default")
      (node (ref "IC3") (pin "10") (pinfunction "~{FLT}_10") (pintype "open_collector"))
    )
    (net (code "97") (name "unconnected-(IC4-~{FLT}-Pad10)") (class "Default")
      (node (ref "IC4") (pin "10") (pinfunction "~{FLT}_10") (pintype "open_collector"))
    )
    (net (code "98") (name "unconnected-(IC5-~{FLT}-Pad10)") (class "Default")
      (node (ref "IC5") (pin "10") (pinfunction "~{FLT}_10") (pintype "open_collector"))
    )
    (net (code "99") (name "unconnected-(IC6-~{FLT}-Pad10)") (class "Default")
      (node (ref "IC6") (pin "10") (pinfunction "~{FLT}_10") (pintype "open_collector"))
    )
    (net (code "100") (name "unconnected-(IC7-~{FLT}-Pad10)") (class "Default")
      (node (ref "IC7") (pin "10") (pinfunction "~{FLT}_10") (pintype "open_collector"))
    )
    (net (code "101") (name "unconnected-(IC8-~{FLT}-Pad10)") (class "Default")
      (node (ref "IC8") (pin "10") (pinfunction "~{FLT}_10") (pintype "open_collector"))
    )
    (net (code "102") (name "unconnected-(IC9-~{FLT}-Pad10)") (class "Default")
      (node (ref "IC9") (pin "10") (pinfunction "~{FLT}_10") (pintype "open_collector"))
    )
    (net (code "103") (name "unconnected-(IC10-~{FLT}-Pad10)") (class "Default")
      (node (ref "IC10") (pin "10") (pinfunction "~{FLT}_10") (pintype "open_collector"))
    )
    (net (code "104") (name "unconnected-(IC11A-G-Pad1)") (class "Default")
      (node (ref "IC11") (pin "1") (pinfunction "G_1") (pintype "input"))
    )
    (net (code "105") (name "unconnected-(IC11A-Y3-Pad7)") (class "Default")
      (node (ref "IC11") (pin "7") (pinfunction "Y3_7") (pintype "output"))
    )
    (net (code "106") (name "unconnected-(U$2-PadDT)") (class "Default")
      (node (ref "U$2") (pin "DT") (pinfunction "DT_DT") (pintype "bidirectional"))
    )
    (net (code "107") (name "unconnected-(U$2-PadSCK)") (class "Default")
      (node (ref "U$2") (pin "SCK") (pinfunction "SCK_SCK") (pintype "bidirectional"))
    )
    (net (code "108") (name "unconnected-(U1-3V3-Pad1)") (class "Default")
      (node (ref "U1") (pin "1") (pinfunction "3V3_1") (pintype "output"))
    )
    (net (code "109") (name "unconnected-(U1-D33-Pad22)") (class "Default")
      (node (ref "U1") (pin "22") (pinfunction "D33_22") (pintype "bidirectional"))
    )
    (net (code "110") (name "unconnected-(U1-EN-Pad16)") (class "Default")
      (node (ref "U1") (pin "16") (pinfunction "EN_16") (pintype "input"))
    )
  )
)
